# 04_Mechanical.net
KiCad netlist of a schematic drawn in Altium Designer
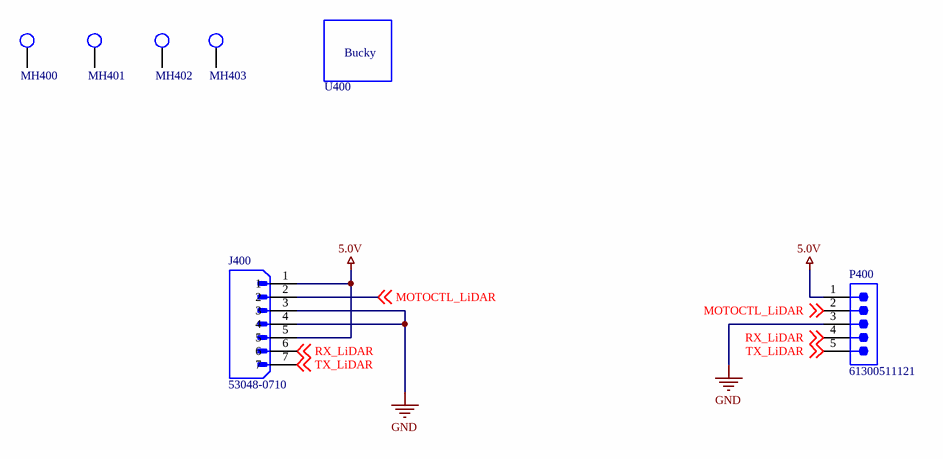
[diagram p0: 04_Mechanical.SchDoc]

(export (version "E")
  (design (tool "Eeschema 10.0.6"))
  (components
    (comp (ref "J400")
      (value "53048-0710")
      (footprint "MOLEX_530480710")
      (description "7-Pin 1.25mm Molex Connector")
      (fields (field (name "MP") "530480710"))
      (libsource (lib "ECE453_S24") (part "53048-0710"))
    )
    (comp (ref "MH400")
      (value "MHOLE_2_55MM")
      (footprint "MHOLE_2_55MM")
      (description "Mounting Holde")
      (fields (field (name "MANUFACTURER PART NUMBER") "UW MTHOLE"))
      (libsource (lib "ECE453_S24") (part "MHOLE_2_55MM"))
    )
    (comp (ref "MH401")
      (value "MHOLE_2_55MM")
      (footprint "MHOLE_2_55MM")
      (description "Mounting Holde")
      (fields (field (name "MANUFACTURER PART NUMBER") "UW MTHOLE"))
      (libsource (lib "ECE453_S24") (part "MHOLE_2_55MM"))
    )
    (comp (ref "MH402")
      (value "MHOLE_2_55MM")
      (footprint "MHOLE_2_55MM")
      (description "Mounting Holde")
      (fields (field (name "MANUFACTURER PART NUMBER") "UW MTHOLE"))
      (libsource (lib "ECE453_S24") (part "MHOLE_2_55MM"))
    )
    (comp (ref "MH403")
      (value "MHOLE_2_55MM")
      (footprint "MHOLE_2_55MM")
      (description "Mounting Holde")
      (fields (field (name "MANUFACTURER PART NUMBER") "UW MTHOLE"))
      (libsource (lib "ECE453_S24") (part "MHOLE_2_55MM"))
    )
    (comp (ref "P400")
      (value "61300511121")
      (footprint "61300511121")
      (libsource (lib "Altium Content Vault") (part "Header_Male_1R_05P"))
    )
    (comp (ref "U400")
      (value "Bucky")
      (footprint "WalkingBucky")
      (description "Bucky Badger Image")
      (fields (field (name "MANUFACTURER PART NUMBER") "UW Bucky"))
      (libsource (lib "ECE453") (part "Bucky"))
    )
  )
  (nets
    (net (code "1") (name "5.0V") (class "Default")
      (node (ref "J400") (pin "1") (pinfunction "1_1") (pintype "passive"))
      (node (ref "J400") (pin "5") (pinfunction "5_5") (pintype "passive"))
      (node (ref "P400") (pin "1") (pinfunction "1_1") (pintype "passive"))
    )
    (net (code "2") (name "GND") (class "Default")
      (node (ref "J400") (pin "3") (pinfunction "3_3") (pintype "passive"))
      (node (ref "J400") (pin "4") (pinfunction "4_4") (pintype "passive"))
      (node (ref "P400") (pin "3") (pinfunction "3_3") (pintype "passive"))
    )
    (net (code "3") (name "MOTOCTL_LiDAR") (class "Default")
      (node (ref "J400") (pin "2") (pinfunction "2_2") (pintype "passive"))
      (node (ref "P400") (pin "2") (pinfunction "2_2") (pintype "passive"))
    )
    (net (code "4") (name "RX_LiDAR") (class "Default")
      (node (ref "J400") (pin "6") (pinfunction "6_6") (pintype "passive"))
      (node (ref "P400") (pin "4") (pinfunction "4_4") (pintype "passive"))
    )
    (net (code "5") (name "TX_LiDAR") (class "Default")
      (node (ref "J400") (pin "7") (pinfunction "7_7") (pintype "passive"))
      (node (ref "P400") (pin "5") (pinfunction "5_5") (pintype "passive"))
    )
    (net (code "6") (name "unconnected-(MH400-Pad1)") (class "Default")
      (node (ref "MH400") (pin "1") (pintype "passive"))
    )
    (net (code "7") (name "unconnected-(MH401-Pad1)") (class "Default")
      (node (ref "MH401") (pin "1") (pintype "passive"))
    )
    (net (code "8") (name "unconnected-(MH402-Pad1)") (class "Default")
      (node (ref "MH402") (pin "1") (pintype "passive"))
    )
    (net (code "9") (name "unconnected-(MH403-Pad1)") (class "Default")
      (node (ref "MH403") (pin "1") (pintype "passive"))
    )
  )
)
